# peri.net
KiCad netlist of a schematic drawn in Altium Designer
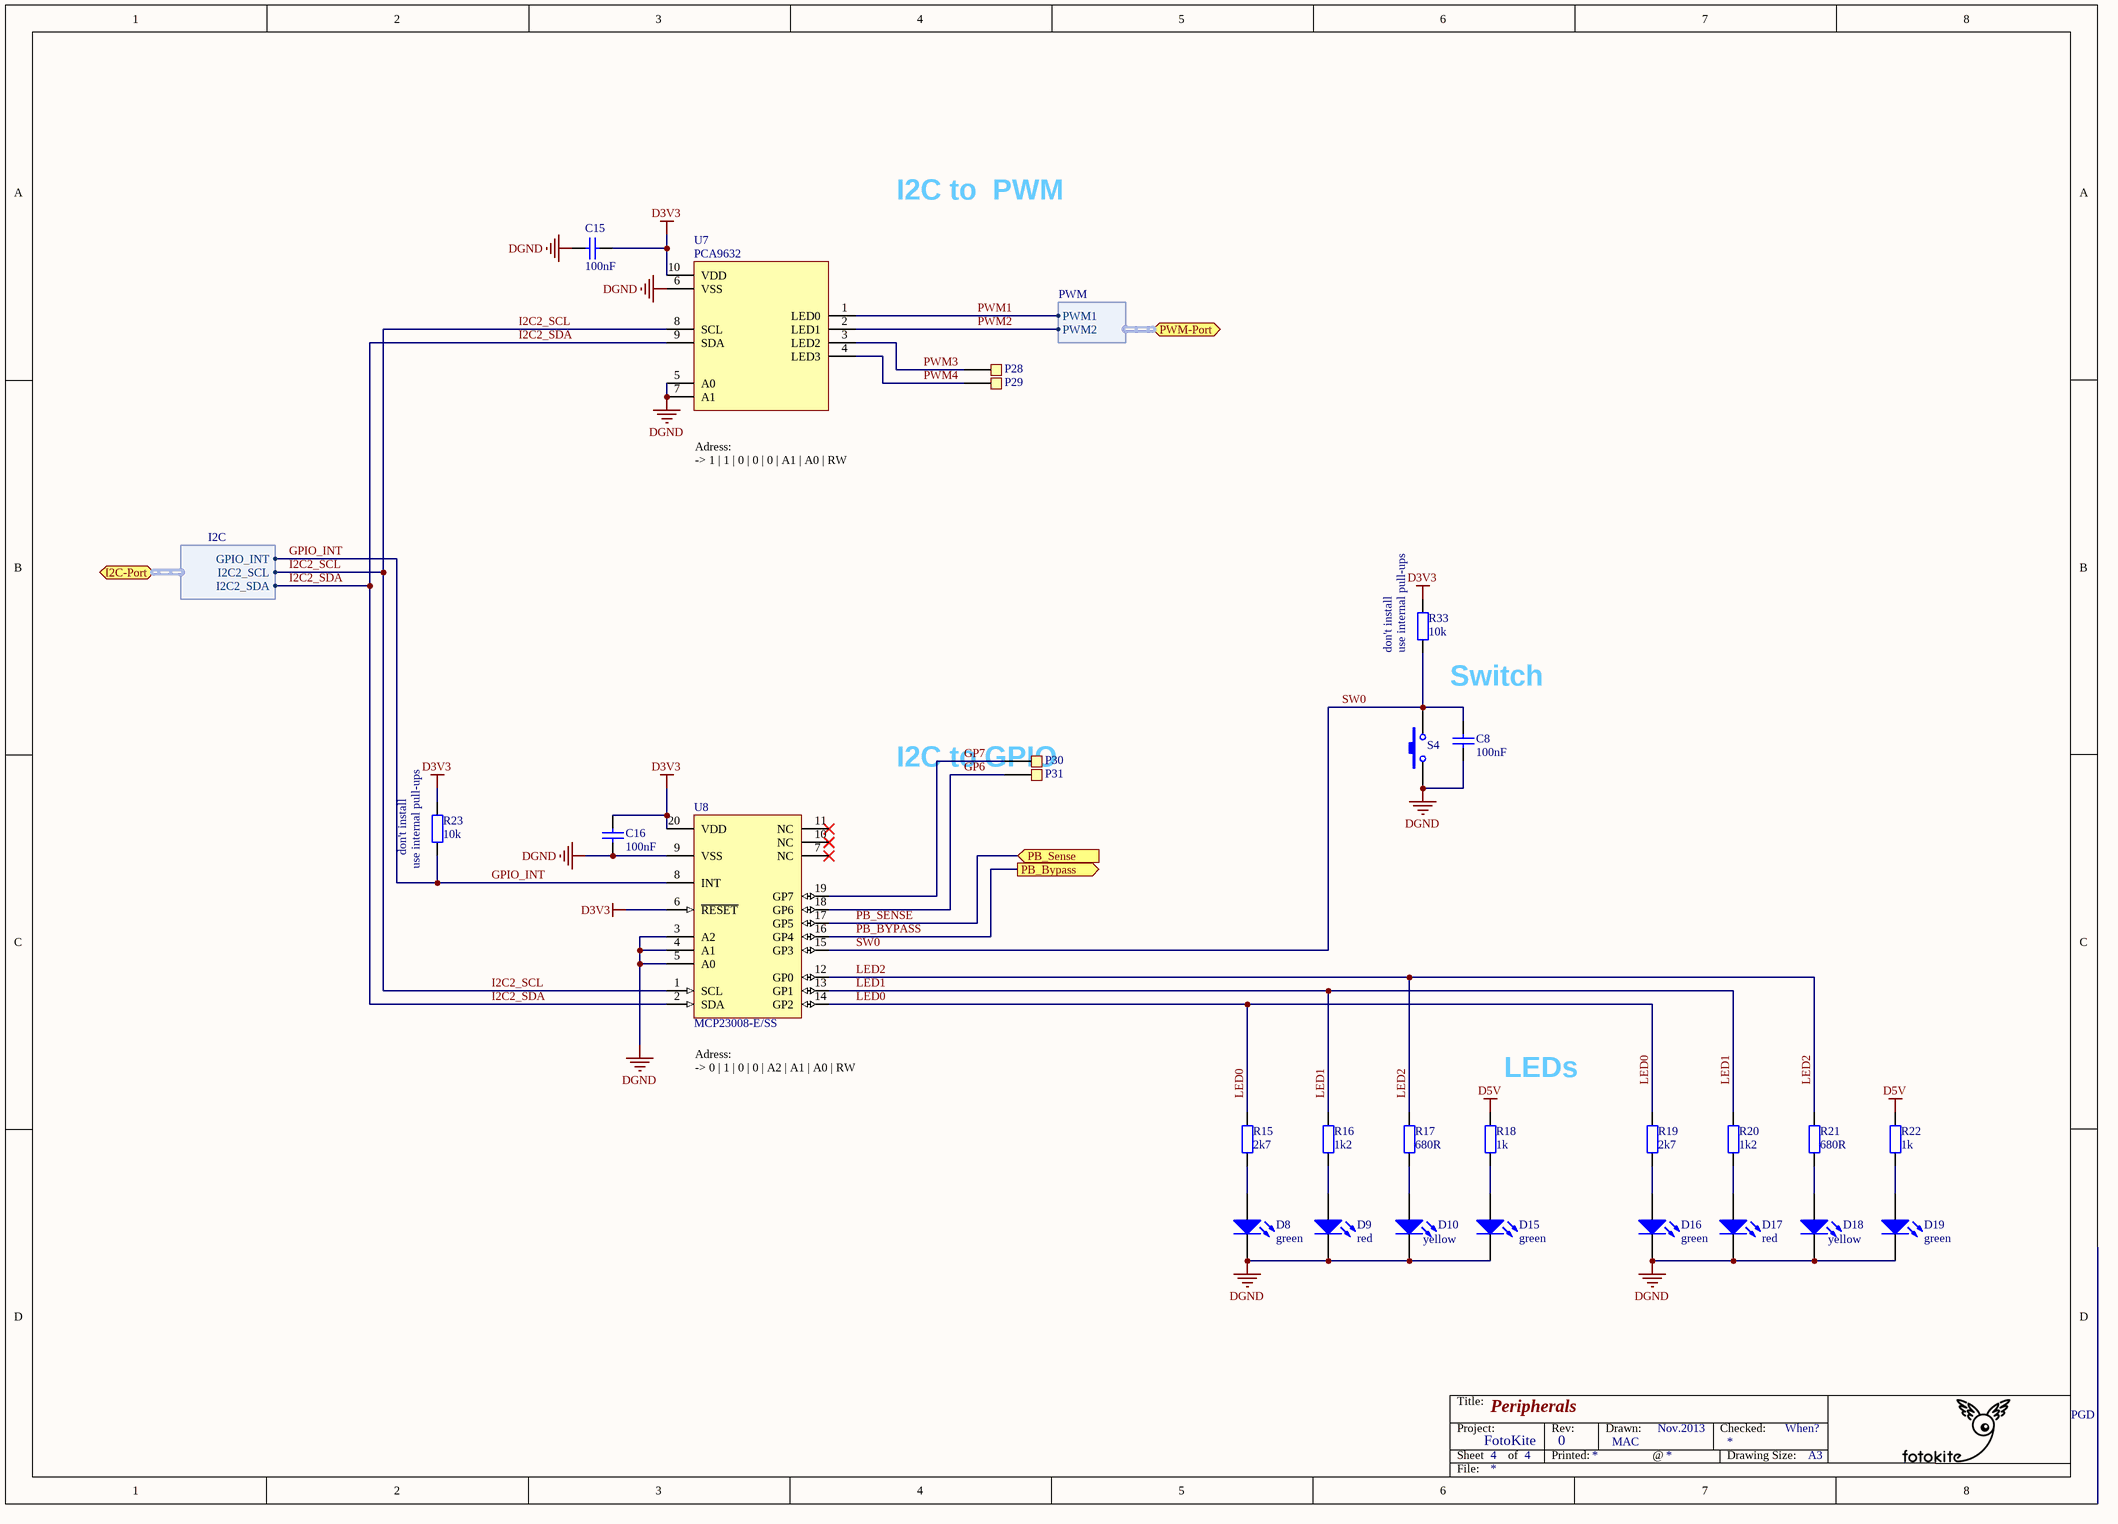
[diagram p0: peri.SchDoc]

(export (version "E")
  (design (tool "Eeschema 10.0.6"))
  (components
    (comp (ref "C8")
      (value "100nF")
      (footprint "CAP_0603i_1608m -N")
      (description "capacitor")
      (libsource (lib "IDSC std generic parts ") (part "Cap"))
    )
    (comp (ref "C15")
      (value "100nF")
      (footprint "CAP_0603i_1608m -N")
      (description "capacitor")
      (libsource (lib "IDSC std generic parts ") (part "Cap"))
    )
    (comp (ref "C16")
      (value "100nF")
      (footprint "CAP_0603i_1608m -N")
      (description "capacitor")
      (libsource (lib "IDSC std generic parts ") (part "Cap"))
    )
    (comp (ref "D8")
      (value "Diode LED green")
      (footprint "LED_LTST_SIDE")
      (description "LED")
      (fields (field (name "COLOUR") "green"))
      (libsource (lib "IDSC std generic parts ") (part "Diode LED"))
    )
    (comp (ref "D9")
      (value "Diode LED red")
      (footprint "LED_LTST_SIDE")
      (description "LED")
      (fields (field (name "COLOUR") "red"))
      (libsource (lib "IDSC std generic parts ") (part "Diode LED"))
    )
    (comp (ref "D10")
      (value "Diode LED yellow")
      (footprint "LED_LTST_SIDE")
      (description "LED")
      (fields (field (name "COLOUR") "yellow"))
      (libsource (lib "IDSC std generic parts ") (part "Diode LED"))
    )
    (comp (ref "D15")
      (value "Diode LED green")
      (footprint "LED_LTST_SIDE")
      (description "LED")
      (fields (field (name "COLOUR") "green"))
      (libsource (lib "IDSC std generic parts ") (part "Diode LED"))
    )
    (comp (ref "D16")
      (value "Diode LED green")
      (footprint "LED_LTST_SIDE")
      (description "LED")
      (fields (field (name "COLOUR") "green"))
      (libsource (lib "IDSC std generic parts ") (part "Diode LED"))
    )
    (comp (ref "D17")
      (value "Diode LED red")
      (footprint "LED_LTST_SIDE")
      (description "LED")
      (fields (field (name "COLOUR") "red"))
      (libsource (lib "IDSC std generic parts ") (part "Diode LED"))
    )
    (comp (ref "D18")
      (value "Diode LED yellow")
      (footprint "LED_LTST_SIDE")
      (description "LED")
      (fields (field (name "COLOUR") "yellow"))
      (libsource (lib "IDSC std generic parts ") (part "Diode LED"))
    )
    (comp (ref "D19")
      (value "Diode LED green")
      (footprint "LED_LTST_SIDE")
      (description "LED")
      (fields (field (name "COLOUR") "green"))
      (libsource (lib "IDSC std generic parts ") (part "Diode LED"))
    )
    (comp (ref "P28")
      (value "Pad")
      (footprint "Pad_0603")
      (description "Single Pad or Testpoint")
      (libsource (lib "IDSC std connectors") (part "Pad"))
    )
    (comp (ref "P29")
      (value "Pad")
      (footprint "Pad_0603")
      (description "Single Pad or Testpoint")
      (libsource (lib "IDSC std connectors") (part "Pad"))
    )
    (comp (ref "P30")
      (value "Pad")
      (footprint "Pad_0603")
      (description "Single Pad or Testpoint")
      (libsource (lib "IDSC std connectors") (part "Pad"))
    )
    (comp (ref "P31")
      (value "Pad")
      (footprint "Pad_0603")
      (description "Single Pad or Testpoint")
      (libsource (lib "IDSC std connectors") (part "Pad"))
    )
    (comp (ref "R15")
      (value "2k7")
      (footprint "RES_0603i_1608m -N")
      (description "Resistor")
      (libsource (lib "IDSC std generic parts ") (part "Res"))
    )
    (comp (ref "R16")
      (value "1k2")
      (footprint "RES_0603i_1608m -N")
      (description "Resistor")
      (libsource (lib "IDSC std generic parts ") (part "Res"))
    )
    (comp (ref "R17")
      (value "680R")
      (footprint "RES_0603i_1608m -N")
      (description "Resistor")
      (libsource (lib "IDSC std generic parts ") (part "Res"))
    )
    (comp (ref "R18")
      (value "1k")
      (footprint "RES_0603i_1608m -N")
      (description "Resistor")
      (libsource (lib "IDSC std generic parts ") (part "Res"))
    )
    (comp (ref "R19")
      (value "2k7")
      (footprint "RES_0603i_1608m -N")
      (description "Resistor")
      (libsource (lib "IDSC std generic parts ") (part "Res"))
    )
    (comp (ref "R20")
      (value "1k2")
      (footprint "RES_0603i_1608m -N")
      (description "Resistor")
      (libsource (lib "IDSC std generic parts ") (part "Res"))
    )
    (comp (ref "R21")
      (value "680R")
      (footprint "RES_0603i_1608m -N")
      (description "Resistor")
      (libsource (lib "IDSC std generic parts ") (part "Res"))
    )
    (comp (ref "R22")
      (value "1k")
      (footprint "RES_0603i_1608m -N")
      (description "Resistor")
      (libsource (lib "IDSC std generic parts ") (part "Res"))
    )
    (comp (ref "R23")
      (value "10k")
      (footprint "RES_0603i_1608m -N")
      (description "Resistor")
      (fields (field (name "NOTE") "don't install") (field (name "NOTE2") "use internal pull-ups"))
      (libsource (lib "IDSC std generic parts ") (part "Res"))
    )
    (comp (ref "R33")
      (value "10k")
      (footprint "RES_0603i_1608m -N")
      (description "Resistor")
      (fields (field (name "NOTE") "don't install") (field (name "NOTE2") "use internal pull-ups"))
      (libsource (lib "IDSC std generic parts ") (part "Res"))
    )
    (comp (ref "S4")
      (value "EVQ-PUB02K")
      (footprint "EVQPU")
      (description "Switch")
      (libsource (lib "IDSC std generic parts ") (part "SW PB"))
    )
    (comp (ref "U7")
      (value "PCA9632")
      (footprint "TSSOP10_L")
      (description "0.4A Dual H-Bridge")
      (fields (field (name "MANUFACTURER") "Freescale Semiconductor"))
      (libsource (lib "IDSC_component_lib") (part "PCA9632"))
    )
    (comp (ref "U8")
      (value "MCP23008-E/SS")
      (footprint "SSOP-SS20_N")
      (description "8-Bit I/O Expander with Serial Interface, 20-Pin SSOP, Extended Temperature")
      (libsource (lib "Altium Content Vault") (part "CMP-0186-00169-3"))
    )
  )
  (nets
    (net (code "3") (name "/GP6") (class "Default")
      (node (ref "P31") (pin "1") (pinfunction "1_1") (pintype "passive"))
      (node (ref "U8") (pin "18") (pinfunction "GP6_18") (pintype "bidirectional"))
    )
    (net (code "4") (name "/GP7") (class "Default")
      (node (ref "P30") (pin "1") (pinfunction "1_1") (pintype "passive"))
      (node (ref "U8") (pin "19") (pinfunction "GP7_19") (pintype "bidirectional"))
    )
    (net (code "5") (name "/GPIO_INT") (class "Default")
      (node (ref "R23") (pin "1") (pinfunction "1_1") (pintype "passive"))
      (node (ref "U8") (pin "8") (pinfunction "INT_8") (pintype "open_collector"))
    )
    (net (code "6") (name "/I2C2_SCL") (class "Default")
      (node (ref "U7") (pin "8") (pinfunction "SCL_8") (pintype "passive"))
      (node (ref "U8") (pin "1") (pinfunction "SCL_1") (pintype "input"))
    )
    (net (code "7") (name "/I2C2_SDA") (class "Default")
      (node (ref "U7") (pin "9") (pinfunction "SDA_9") (pintype "passive"))
      (node (ref "U8") (pin "2") (pinfunction "SDA_2") (pintype "input"))
    )
    (net (code "8") (name "/LED0") (class "Default")
      (node (ref "R15") (pin "2") (pinfunction "2_2") (pintype "passive"))
      (node (ref "R19") (pin "2") (pinfunction "2_2") (pintype "passive"))
      (node (ref "U8") (pin "14") (pinfunction "GP2_14") (pintype "bidirectional"))
    )
    (net (code "9") (name "/LED1") (class "Default")
      (node (ref "R16") (pin "2") (pinfunction "2_2") (pintype "passive"))
      (node (ref "R20") (pin "2") (pinfunction "2_2") (pintype "passive"))
      (node (ref "U8") (pin "13") (pinfunction "GP1_13") (pintype "bidirectional"))
    )
    (net (code "10") (name "/LED2") (class "Default")
      (node (ref "R17") (pin "2") (pinfunction "2_2") (pintype "passive"))
      (node (ref "R21") (pin "2") (pinfunction "2_2") (pintype "passive"))
      (node (ref "U8") (pin "12") (pinfunction "GP0_12") (pintype "bidirectional"))
    )
    (net (code "11") (name "/PB_BYPASS") (class "Default")
      (node (ref "U8") (pin "16") (pinfunction "GP4_16") (pintype "bidirectional"))
    )
    (net (code "12") (name "/PB_SENSE") (class "Default")
      (node (ref "U8") (pin "17") (pinfunction "GP5_17") (pintype "bidirectional"))
    )
    (net (code "13") (name "/PWM1") (class "Default")
      (node (ref "U7") (pin "1") (pinfunction "LED0_1") (pintype "passive"))
    )
    (net (code "14") (name "/PWM2") (class "Default")
      (node (ref "U7") (pin "2") (pinfunction "LED1_2") (pintype "passive"))
    )
    (net (code "15") (name "/PWM3") (class "Default")
      (node (ref "P28") (pin "1") (pinfunction "1_1") (pintype "passive"))
      (node (ref "U7") (pin "3") (pinfunction "LED2_3") (pintype "passive"))
    )
    (net (code "16") (name "/PWM4") (class "Default")
      (node (ref "P29") (pin "1") (pinfunction "1_1") (pintype "passive"))
      (node (ref "U7") (pin "4") (pinfunction "LED3_4") (pintype "passive"))
    )
    (net (code "17") (name "/SW0") (class "Default")
      (node (ref "C8") (pin "2") (pinfunction "2_2") (pintype "passive"))
      (node (ref "R33") (pin "1") (pinfunction "1_1") (pintype "passive"))
      (node (ref "S4") (pin "1") (pinfunction "1_1") (pintype "passive"))
      (node (ref "U8") (pin "15") (pinfunction "GP3_15") (pintype "bidirectional"))
    )
    (net (code "20") (name "D3V3") (class "Default")
      (node (ref "C15") (pin "1") (pinfunction "1_1") (pintype "passive"))
      (node (ref "C16") (pin "1") (pinfunction "1_1") (pintype "passive"))
      (node (ref "R23") (pin "2") (pinfunction "2_2") (pintype "passive"))
      (node (ref "R33") (pin "2") (pinfunction "2_2") (pintype "passive"))
      (node (ref "U7") (pin "10") (pinfunction "VDD_10") (pintype "power_in"))
      (node (ref "U8") (pin "20") (pinfunction "VDD_20") (pintype "power_in"))
      (node (ref "U8") (pin "6") (pinfunction "~{RESET}_6") (pintype "input"))
    )
    (net (code "21") (name "D5V") (class "Default")
      (node (ref "R18") (pin "2") (pinfunction "2_2") (pintype "passive"))
      (node (ref "R22") (pin "2") (pinfunction "2_2") (pintype "passive"))
    )
    (net (code "22") (name "DGND") (class "Default")
      (node (ref "C15") (pin "2") (pinfunction "2_2") (pintype "passive"))
      (node (ref "C16") (pin "2") (pinfunction "2_2") (pintype "passive"))
      (node (ref "C8") (pin "1") (pinfunction "1_1") (pintype "passive"))
      (node (ref "D10") (pin "2") (pinfunction "K_2") (pintype "passive"))
      (node (ref "D15") (pin "2") (pinfunction "K_2") (pintype "passive"))
      (node (ref "D16") (pin "2") (pinfunction "K_2") (pintype "passive"))
      (node (ref "D17") (pin "2") (pinfunction "K_2") (pintype "passive"))
      (node (ref "D18") (pin "2") (pinfunction "K_2") (pintype "passive"))
      (node (ref "D19") (pin "2") (pinfunction "K_2") (pintype "passive"))
      (node (ref "D8") (pin "2") (pinfunction "K_2") (pintype "passive"))
      (node (ref "D9") (pin "2") (pinfunction "K_2") (pintype "passive"))
      (node (ref "S4") (pin "2") (pinfunction "2_2") (pintype "passive"))
      (node (ref "U7") (pin "5") (pinfunction "A0_5") (pintype "passive"))
      (node (ref "U7") (pin "6") (pinfunction "VSS_6") (pintype "power_in"))
      (node (ref "U7") (pin "7") (pinfunction "A1_7") (pintype "passive"))
      (node (ref "U8") (pin "3") (pinfunction "A2_3") (pintype "passive"))
      (node (ref "U8") (pin "4") (pinfunction "A1_4") (pintype "passive"))
      (node (ref "U8") (pin "5") (pinfunction "A0_5") (pintype "passive"))
      (node (ref "U8") (pin "9") (pinfunction "VSS_9") (pintype "power_in"))
    )
    (net (code "23") (name "Net-(D8-A)") (class "Default")
      (node (ref "D8") (pin "1") (pinfunction "A_1") (pintype "passive"))
      (node (ref "R15") (pin "1") (pinfunction "1_1") (pintype "passive"))
    )
    (net (code "24") (name "Net-(D9-A)") (class "Default")
      (node (ref "D9") (pin "1") (pinfunction "A_1") (pintype "passive"))
      (node (ref "R16") (pin "1") (pinfunction "1_1") (pintype "passive"))
    )
    (net (code "25") (name "Net-(D10-A)") (class "Default")
      (node (ref "D10") (pin "1") (pinfunction "A_1") (pintype "passive"))
      (node (ref "R17") (pin "1") (pinfunction "1_1") (pintype "passive"))
    )
    (net (code "26") (name "Net-(D15-A)") (class "Default")
      (node (ref "D15") (pin "1") (pinfunction "A_1") (pintype "passive"))
      (node (ref "R18") (pin "1") (pinfunction "1_1") (pintype "passive"))
    )
    (net (code "27") (name "Net-(D16-A)") (class "Default")
      (node (ref "D16") (pin "1") (pinfunction "A_1") (pintype "passive"))
      (node (ref "R19") (pin "1") (pinfunction "1_1") (pintype "passive"))
    )
    (net (code "28") (name "Net-(D17-A)") (class "Default")
      (node (ref "D17") (pin "1") (pinfunction "A_1") (pintype "passive"))
      (node (ref "R20") (pin "1") (pinfunction "1_1") (pintype "passive"))
    )
    (net (code "29") (name "Net-(D18-A)") (class "Default")
      (node (ref "D18") (pin "1") (pinfunction "A_1") (pintype "passive"))
      (node (ref "R21") (pin "1") (pinfunction "1_1") (pintype "passive"))
    )
    (net (code "30") (name "Net-(D19-A)") (class "Default")
      (node (ref "D19") (pin "1") (pinfunction "A_1") (pintype "passive"))
      (node (ref "R22") (pin "1") (pinfunction "1_1") (pintype "passive"))
    )
    (net (code "31") (name "unconnected-(U8-NC-Pad7)") (class "Default")
      (node (ref "U8") (pin "7") (pinfunction "NC_7") (pintype "passive+no_connect"))
    )
    (net (code "32") (name "unconnected-(U8-NC-Pad10)") (class "Default")
      (node (ref "U8") (pin "10") (pinfunction "NC_10") (pintype "passive+no_connect"))
    )
    (net (code "33") (name "unconnected-(U8-NC-Pad11)") (class "Default")
      (node (ref "U8") (pin "11") (pinfunction "NC_11") (pintype "passive+no_connect"))
    )
  )
)
